# MCU_Supply.net
KiCad netlist of a schematic drawn in Altium Designer
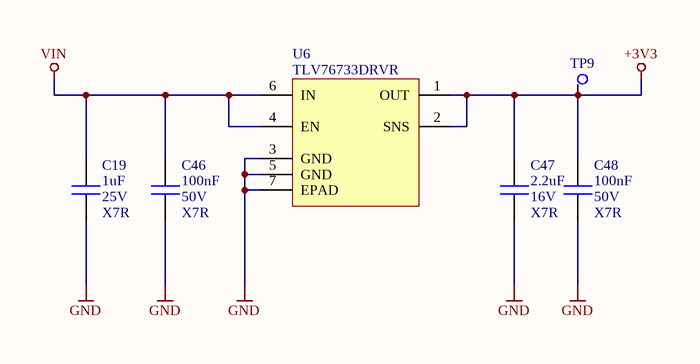
[diagram p0: MCU_Supply.SchDoc]

(export (version "E")
  (design (tool "Eeschema 10.0.6"))
  (components
    (comp (ref "C19")
      (value "1uF")
      (footprint "C_0603")
      (description "Capacitor")
      (fields
        (field (name "VOLTAGE") "25V")
        (field (name "DIELECTRIC") "X7R")
        (field (name "PART NUMBER") "C_1uF_25V_0603")
        (field (name "MANUFACTURER") "Murata")
      )
      (libsource (lib "ProgresjaSpace") (part "C"))
    )
    (comp (ref "C46")
      (value "100nF")
      (footprint "C_0603")
      (description "Capacitor")
      (fields
        (field (name "VOLTAGE") "50V")
        (field (name "DIELECTRIC") "X7R")
        (field (name "PART NUMBER") "C_100nF_50V_0603")
        (field (name "MANUFACTURER") "Kemet")
      )
      (libsource (lib "ProgresjaSpace") (part "C"))
    )
    (comp (ref "C47")
      (value "2.2uF")
      (footprint "C_0805")
      (description "Capacitor")
      (fields
        (field (name "VOLTAGE") "16V")
        (field (name "DIELECTRIC") "X7R")
        (field (name "PART NUMBER") "C_2.2uF_16V_0805")
        (field (name "MANUFACTURER") "Kemet")
      )
      (libsource (lib "ProgresjaSpace") (part "C"))
    )
    (comp (ref "C48")
      (value "100nF")
      (footprint "C_0603")
      (description "Capacitor")
      (fields
        (field (name "VOLTAGE") "50V")
        (field (name "DIELECTRIC") "X7R")
        (field (name "PART NUMBER") "C_100nF_50V_0603")
        (field (name "MANUFACTURER") "Kemet")
      )
      (libsource (lib "ProgresjaSpace") (part "C"))
    )
    (comp (ref "TP9")
      (value "TP_TestPoint")
      (footprint "TP_01")
      (fields (field (name "PART NUMBER") "TestPoint1") (field (name "MANUFACTURER") "Progresja Space"))
      (libsource (lib "ProgresjaSpace") (part "TP_TestPoint"))
    )
    (comp (ref "U6")
      (value "IC_TLV76733DRVR")
      (footprint "WSON_6")
      (description "3.3V LDO Voltage Regulator")
      (fields
        (field (name "=VALUE") "TLV76733DRVR")
        (field (name "PART NUMBER") "TLV76733DRVR")
        (field (name "MANUFACTURER") "TI")
      )
      (libsource (lib "ProgresjaSpace") (part "IC_TLV76733DRVR"))
    )
  )
  (nets
    (net (code "1") (name "+3V3") (class "Default")
      (node (ref "C47") (pin "1") (pinfunction "1_1") (pintype "passive"))
      (node (ref "C48") (pin "1") (pinfunction "1_1") (pintype "passive"))
      (node (ref "TP9") (pin "1") (pinfunction "1_1") (pintype "passive"))
      (node (ref "U6") (pin "1") (pinfunction "OUT_1") (pintype "passive"))
      (node (ref "U6") (pin "2") (pinfunction "SNS_2") (pintype "passive"))
    )
    (net (code "2") (name "GND") (class "Default")
      (node (ref "C19") (pin "2") (pinfunction "2_2") (pintype "passive"))
      (node (ref "C46") (pin "2") (pinfunction "2_2") (pintype "passive"))
      (node (ref "C47") (pin "2") (pinfunction "2_2") (pintype "passive"))
      (node (ref "C48") (pin "2") (pinfunction "2_2") (pintype "passive"))
      (node (ref "U6") (pin "3") (pinfunction "GND_3") (pintype "passive"))
      (node (ref "U6") (pin "5") (pinfunction "GND_5") (pintype "passive"))
      (node (ref "U6") (pin "7") (pinfunction "EPAD_7") (pintype "passive"))
    )
    (net (code "3") (name "VIN") (class "Default")
      (node (ref "C19") (pin "1") (pinfunction "1_1") (pintype "passive"))
      (node (ref "C46") (pin "1") (pinfunction "1_1") (pintype "passive"))
      (node (ref "U6") (pin "4") (pinfunction "EN_4") (pintype "passive"))
      (node (ref "U6") (pin "6") (pinfunction "IN_6") (pintype "passive"))
    )
  )
)
